# 0X_-_CPU.net
KiCad netlist of a schematic drawn in Altium Designer
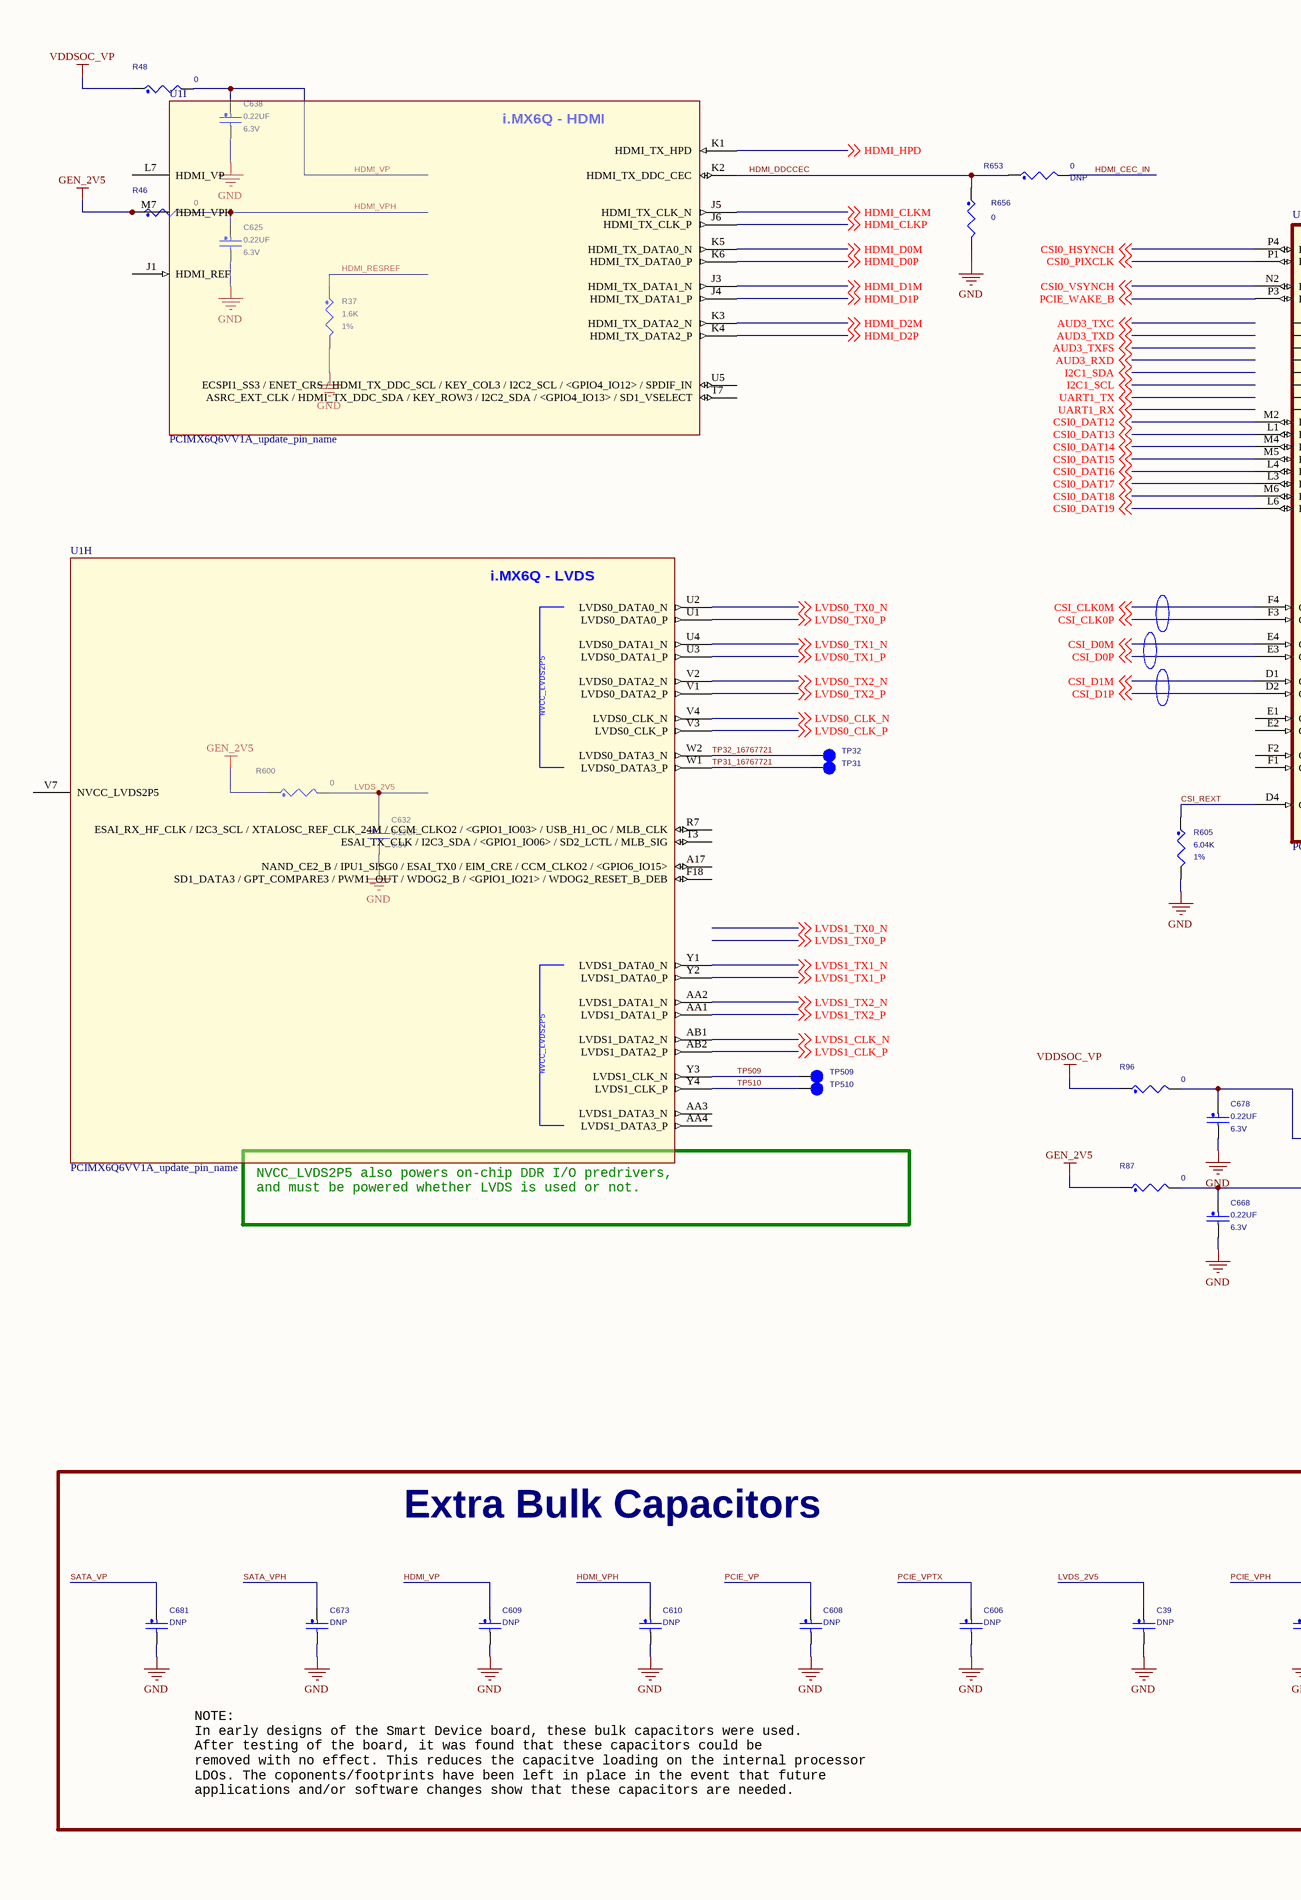
[diagram p0: [0X] - CPU.SchDoc, left]
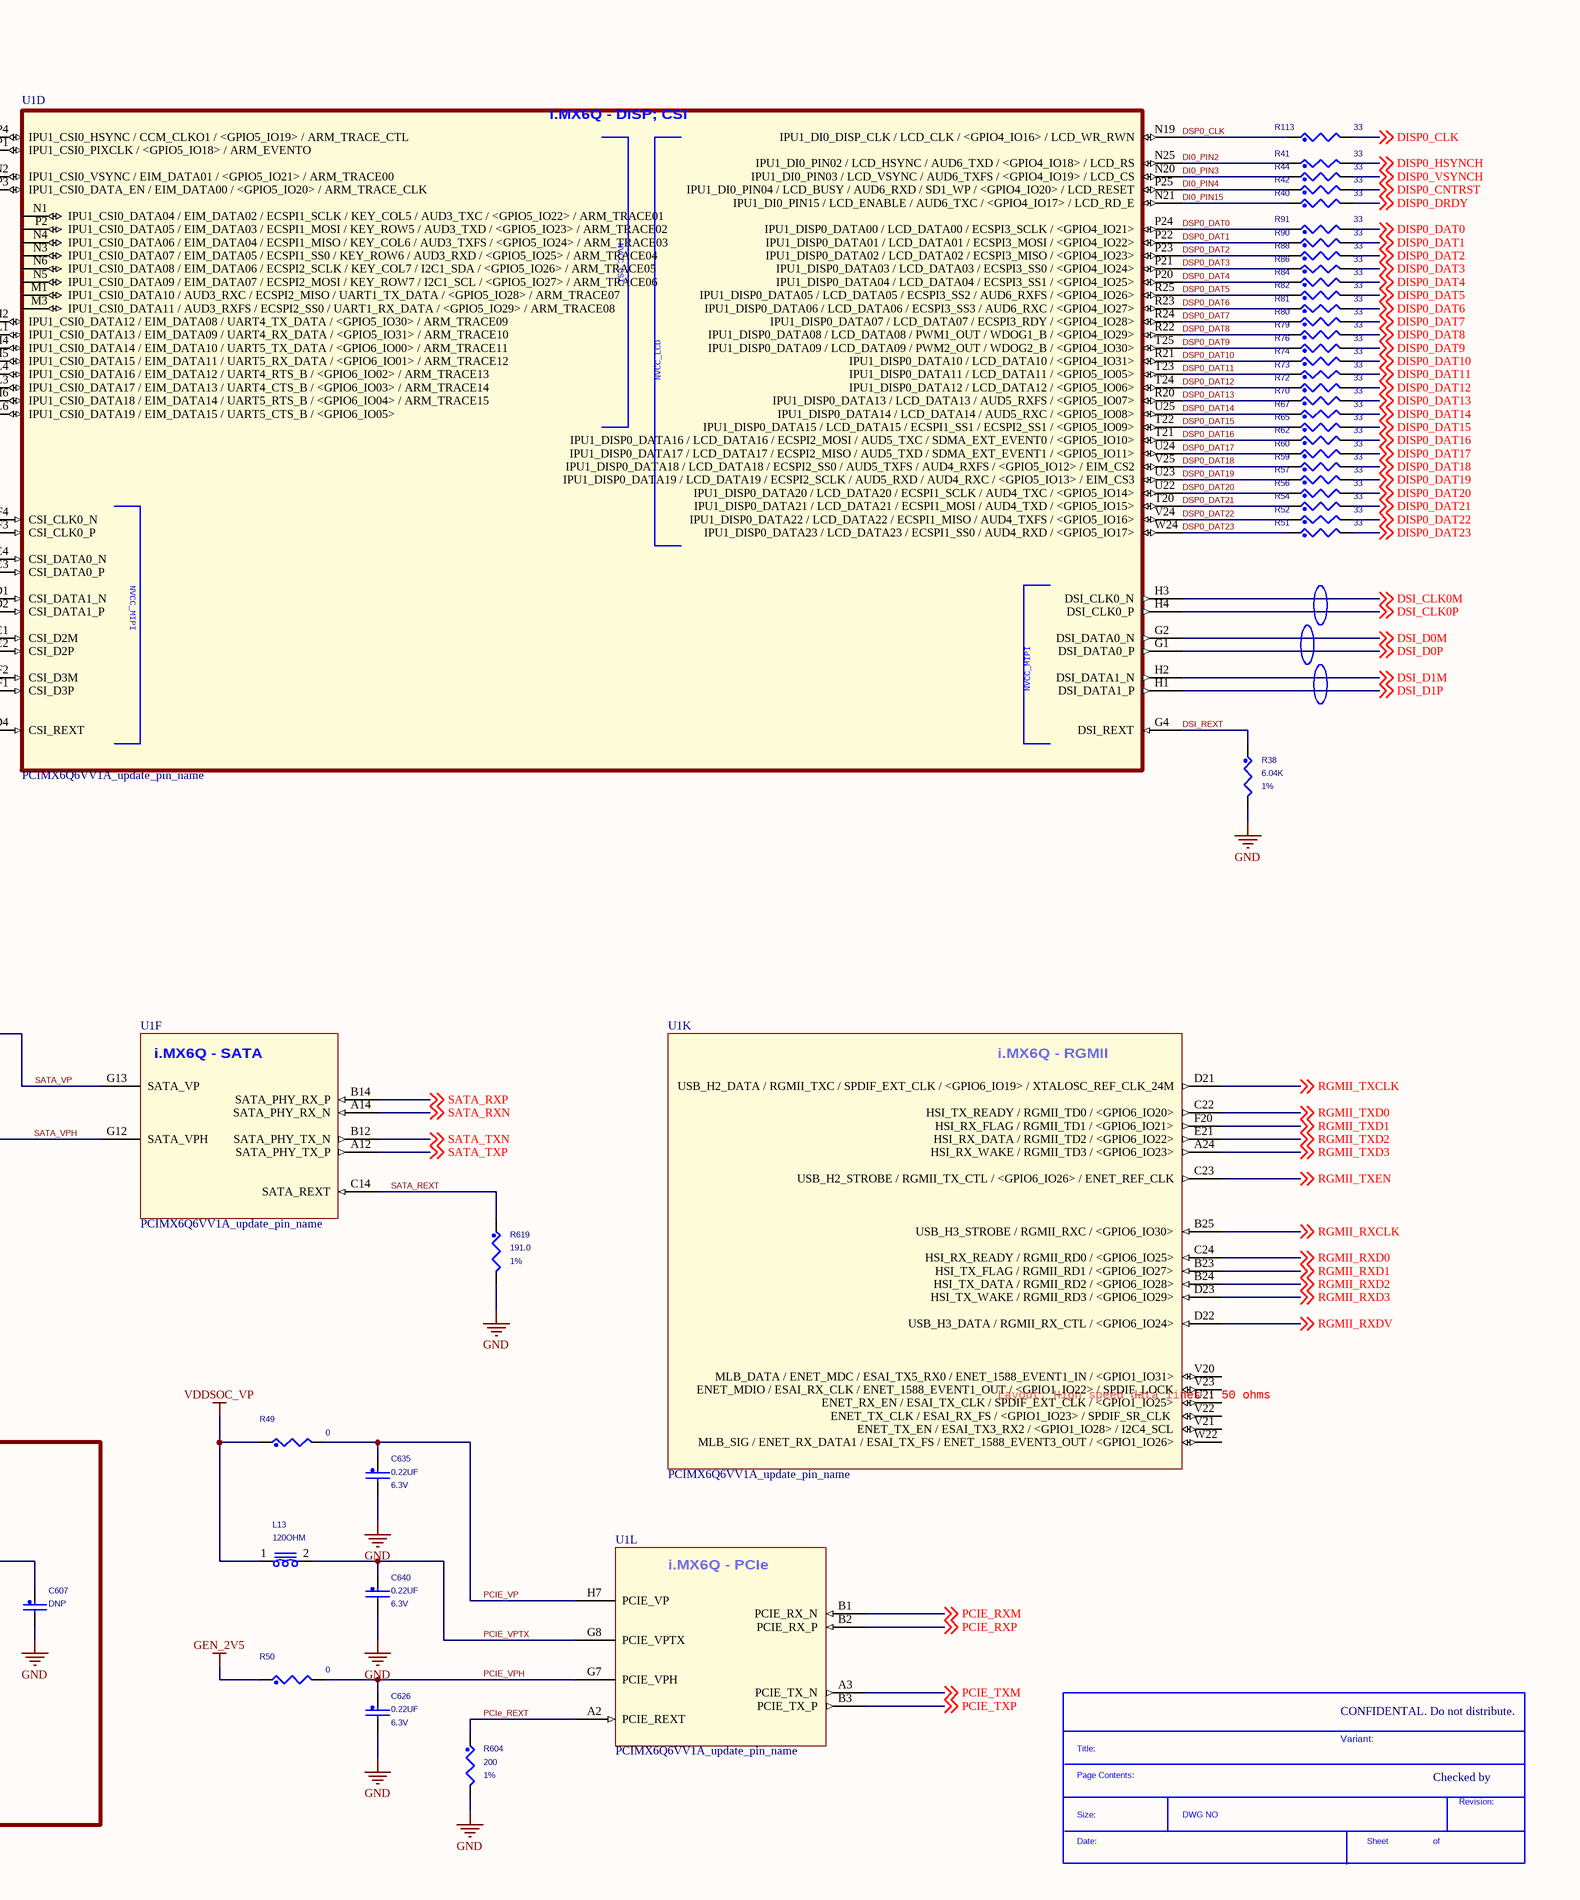
[diagram p1: [0X] - CPU.SchDoc, right]

(export (version "E")
  (design (tool "Eeschema 10.0.6"))
  (components
    (comp (ref "*") (value "SDTitleBlock") (libsource (lib "*") (part "SDTitleBlock")))
    (comp (ref "C39")
      (value "4.7UF")
      (description "CAP CER 4.7UF 10V 10% X5R 0603")
      (fields (field (name "TOLERANCE") "10%") (field (name "ASSY_OPT") "DNP") (field (name "VOLTAGE") "10V"))
      (libsource (lib "*") (part "CAP_NP"))
    )
    (comp (ref "C606")
      (value "4.7UF")
      (description "CAP CER 4.7UF 6.3V 10% X5R 0603")
      (fields
        (field (name "VOLTAGE") "6.3V")
        (field (name "TOLERANCE") "10%")
        (field (name "ASSY_OPT") "DNP")
      )
      (libsource (lib "*") (part "CAP_NP"))
    )
    (comp (ref "C607")
      (value "4.7UF")
      (description "CAP CER 4.7UF 6.3V 10% X5R 0603")
      (fields
        (field (name "VOLTAGE") "6.3V")
        (field (name "TOLERANCE") "10%")
        (field (name "ASSY_OPT") "DNP")
      )
      (libsource (lib "*") (part "CAP_NP"))
    )
    (comp (ref "C608")
      (value "4.7UF")
      (description "CAP CER 4.7UF 6.3V 10% X5R 0603")
      (fields
        (field (name "VOLTAGE") "6.3V")
        (field (name "TOLERANCE") "10%")
        (field (name "ASSY_OPT") "DNP")
      )
      (libsource (lib "*") (part "CAP_NP"))
    )
    (comp (ref "C609")
      (value "4.7UF")
      (description "CAP CER 4.7UF 6.3V 10% X5R 0603")
      (fields
        (field (name "TOLERANCE") "10%")
        (field (name "ASSY_OPT") "DNP")
        (field (name "VOLTAGE") "6.3V")
      )
      (libsource (lib "*") (part "CAP_NP"))
    )
    (comp (ref "C610")
      (value "4.7UF")
      (description "CAP CER 4.7UF 6.3V 10% X5R 0603")
      (fields
        (field (name "ASSY_OPT") "DNP")
        (field (name "TOLERANCE") "10%")
        (field (name "VOLTAGE") "6.3V")
      )
      (libsource (lib "*") (part "CAP_NP"))
    )
    (comp (ref "C625")
      (value "0.22UF")
      (description "CAP CER 0.22UF 6.3V 20% X5R 0201")
      (fields (field (name "VOLTAGE") "6.3V") (field (name "TOLERANCE") "20%") (field (name "WVDC") "6.3V"))
      (libsource (lib "*") (part "CAP_NP"))
    )
    (comp (ref "C626")
      (value "0.22UF")
      (description "CAP CER 0.22UF 6.3V 20% X5R 0201")
      (fields (field (name "WVDC") "6.3V") (field (name "TOLERANCE") "20%") (field (name "VOLTAGE") "6.3V"))
      (libsource (lib "*") (part "CAP_NP"))
    )
    (comp (ref "C632")
      (value "0.22UF")
      (description "CAP CER 0.22UF 6.3V 20% X5R 0201")
      (fields (field (name "VOLTAGE") "6.3V") (field (name "WVDC") "6.3V") (field (name "TOLERANCE") "20%"))
      (libsource (lib "*") (part "CAP_NP"))
    )
    (comp (ref "C635")
      (value "0.22UF")
      (description "CAP CER 0.22UF 6.3V 20% X5R 0201")
      (fields (field (name "WVDC") "6.3V") (field (name "TOLERANCE") "20%") (field (name "VOLTAGE") "6.3V"))
      (libsource (lib "*") (part "CAP_NP"))
    )
    (comp (ref "C638")
      (value "0.22UF")
      (description "CAP CER 0.22UF 6.3V 20% X5R 0201")
      (fields (field (name "VOLTAGE") "6.3V") (field (name "TOLERANCE") "20%") (field (name "WVDC") "6.3V"))
      (libsource (lib "*") (part "CAP_NP"))
    )
    (comp (ref "C640")
      (value "0.22UF")
      (description "CAP CER 0.22UF 6.3V 20% X5R 0201")
      (fields (field (name "WVDC") "6.3V") (field (name "TOLERANCE") "20%") (field (name "VOLTAGE") "6.3V"))
      (libsource (lib "*") (part "CAP_NP"))
    )
    (comp (ref "C668")
      (value "0.22UF")
      (description "CAP CER 0.22UF 6.3V 20% X5R 0201")
      (fields (field (name "VOLTAGE") "6.3V") (field (name "WVDC") "6.3V") (field (name "TOLERANCE") "20%"))
      (libsource (lib "*") (part "CAP_NP"))
    )
    (comp (ref "C673")
      (value "4.7UF")
      (description "CAP CER 4.7UF 6.3V 10% X5R 0603")
      (fields
        (field (name "VOLTAGE") "6.3V")
        (field (name "TOLERANCE") "10%")
        (field (name "ASSY_OPT") "DNP")
      )
      (libsource (lib "*") (part "CAP_NP"))
    )
    (comp (ref "C678")
      (value "0.22UF")
      (description "CAP CER 0.22UF 6.3V 20% X5R 0201")
      (fields (field (name "VOLTAGE") "6.3V") (field (name "WVDC") "6.3V") (field (name "TOLERANCE") "20%"))
      (libsource (lib "*") (part "CAP_NP"))
    )
    (comp (ref "C681")
      (value "4.7UF")
      (description "CAP CER 4.7UF 6.3V 10% X5R 0603")
      (fields
        (field (name "VOLTAGE") "6.3V")
        (field (name "TOLERANCE") "10%")
        (field (name "ASSY_OPT") "DNP")
      )
      (libsource (lib "*") (part "CAP_NP"))
    )
    (comp (ref "L13")
      (value "120OHM")
      (description "IND FER BEAD 120OHM@100MHZ 2A 25% 0603")
      (fields (field (name "TOLERANCE") "25%"))
      (libsource (lib "*") (part "BEAD_0"))
    )
    (comp (ref "R37")
      (value "1.6K")
      (description "RES MF 1.6K  1/16W 1% 0402")
      (fields (field (name "TOLERANCE") "1%"))
      (libsource (lib "*") (part "RES"))
    )
    (comp (ref "R38")
      (value "6.04K")
      (description "RES MF 6.04K  1/16W 1% 0402")
      (fields (field (name "TOLERANCE") "1%"))
      (libsource (lib "*") (part "RES"))
    )
    (comp (ref "R40")
      (value "33")
      (description "RES MF 33 OHM 1/16W 5% 0402")
      (fields (field (name "TOLERANCE") "5%"))
      (libsource (lib "*") (part "RES"))
    )
    (comp (ref "R41")
      (value "33")
      (description "RES MF 33 OHM 1/16W 5% 0402")
      (fields (field (name "TOLERANCE") "5%"))
      (libsource (lib "*") (part "RES"))
    )
    (comp (ref "R42")
      (value "33")
      (description "RES MF 33 OHM 1/16W 5% 0402")
      (fields (field (name "TOLERANCE") "5%"))
      (libsource (lib "*") (part "RES"))
    )
    (comp (ref "R44")
      (value "33")
      (description "RES MF 33 OHM 1/16W 5% 0402")
      (fields (field (name "TOLERANCE") "5%"))
      (libsource (lib "*") (part "RES"))
    )
    (comp (ref "R46")
      (value "0")
      (description "RES MF ZERO OHM 1/10W -- 0402")
      (libsource (lib "*") (part "RES"))
    )
    (comp (ref "R48")
      (value "0")
      (description "RES MF ZERO OHM 1/10W -- 0402")
      (libsource (lib "*") (part "RES"))
    )
    (comp (ref "R49")
      (value "0")
      (description "RES MF ZERO OHM 1/10W -- 0402")
      (libsource (lib "*") (part "RES"))
    )
    (comp (ref "R50")
      (value "0")
      (description "RES MF ZERO OHM 1/10W -- 0402")
      (libsource (lib "*") (part "RES"))
    )
    (comp (ref "R51")
      (value "33")
      (description "RES MF 33 OHM 1/16W 5% 0402")
      (fields (field (name "TOLERANCE") "5%"))
      (libsource (lib "*") (part "RES"))
    )
    (comp (ref "R52")
      (value "33")
      (description "RES MF 33 OHM 1/16W 5% 0402")
      (fields (field (name "TOLERANCE") "5%"))
      (libsource (lib "*") (part "RES"))
    )
    (comp (ref "R54")
      (value "33")
      (description "RES MF 33 OHM 1/16W 5% 0402")
      (fields (field (name "TOLERANCE") "5%"))
      (libsource (lib "*") (part "RES"))
    )
    (comp (ref "R56")
      (value "33")
      (description "RES MF 33 OHM 1/16W 5% 0402")
      (fields (field (name "TOLERANCE") "5%"))
      (libsource (lib "*") (part "RES"))
    )
    (comp (ref "R57")
      (value "33")
      (description "RES MF 33 OHM 1/16W 5% 0402")
      (fields (field (name "TOLERANCE") "5%"))
      (libsource (lib "*") (part "RES"))
    )
    (comp (ref "R59")
      (value "33")
      (description "RES MF 33 OHM 1/16W 5% 0402")
      (fields (field (name "TOLERANCE") "5%"))
      (libsource (lib "*") (part "RES"))
    )
    (comp (ref "R60")
      (value "33")
      (description "RES MF 33 OHM 1/16W 5% 0402")
      (fields (field (name "TOLERANCE") "5%"))
      (libsource (lib "*") (part "RES"))
    )
    (comp (ref "R62")
      (value "33")
      (description "RES MF 33 OHM 1/16W 5% 0402")
      (fields (field (name "TOLERANCE") "5%"))
      (libsource (lib "*") (part "RES"))
    )
    (comp (ref "R65")
      (value "33")
      (description "RES MF 33 OHM 1/16W 5% 0402")
      (fields (field (name "TOLERANCE") "5%"))
      (libsource (lib "*") (part "RES"))
    )
    (comp (ref "R67")
      (value "33")
      (description "RES MF 33 OHM 1/16W 5% 0402")
      (fields (field (name "TOLERANCE") "5%"))
      (libsource (lib "*") (part "RES"))
    )
    (comp (ref "R70")
      (value "33")
      (description "RES MF 33 OHM 1/16W 5% 0402")
      (fields (field (name "TOLERANCE") "5%"))
      (libsource (lib "*") (part "RES"))
    )
    (comp (ref "R72")
      (value "33")
      (description "RES MF 33 OHM 1/16W 5% 0402")
      (fields (field (name "TOLERANCE") "5%"))
      (libsource (lib "*") (part "RES"))
    )
    (comp (ref "R73")
      (value "33")
      (description "RES MF 33 OHM 1/16W 5% 0402")
      (fields (field (name "TOLERANCE") "5%"))
      (libsource (lib "*") (part "RES"))
    )
    (comp (ref "R74")
      (value "33")
      (description "RES MF 33 OHM 1/16W 5% 0402")
      (fields (field (name "TOLERANCE") "5%"))
      (libsource (lib "*") (part "RES"))
    )
    (comp (ref "R76")
      (value "33")
      (description "RES MF 33 OHM 1/16W 5% 0402")
      (fields (field (name "TOLERANCE") "5%"))
      (libsource (lib "*") (part "RES"))
    )
    (comp (ref "R79")
      (value "33")
      (description "RES MF 33 OHM 1/16W 5% 0402")
      (fields (field (name "TOLERANCE") "5%"))
      (libsource (lib "*") (part "RES"))
    )
    (comp (ref "R80")
      (value "33")
      (description "RES MF 33 OHM 1/16W 5% 0402")
      (fields (field (name "TOLERANCE") "5%"))
      (libsource (lib "*") (part "RES"))
    )
    (comp (ref "R81")
      (value "33")
      (description "RES MF 33 OHM 1/16W 5% 0402")
      (fields (field (name "TOLERANCE") "5%"))
      (libsource (lib "*") (part "RES"))
    )
    (comp (ref "R82")
      (value "33")
      (description "RES MF 33 OHM 1/16W 5% 0402")
      (fields (field (name "TOLERANCE") "5%"))
      (libsource (lib "*") (part "RES"))
    )
    (comp (ref "R84")
      (value "33")
      (description "RES MF 33 OHM 1/16W 5% 0402")
      (fields (field (name "TOLERANCE") "5%"))
      (libsource (lib "*") (part "RES"))
    )
    (comp (ref "R86")
      (value "33")
      (description "RES MF 33 OHM 1/16W 5% 0402")
      (fields (field (name "TOLERANCE") "5%"))
      (libsource (lib "*") (part "RES"))
    )
    (comp (ref "R87")
      (value "0")
      (description "RES MF ZERO OHM 1/10W -- 0402")
      (libsource (lib "*") (part "RES"))
    )
    (comp (ref "R88")
      (value "33")
      (description "RES MF 33 OHM 1/16W 5% 0402")
      (fields (field (name "TOLERANCE") "5%"))
      (libsource (lib "*") (part "RES"))
    )
    (comp (ref "R90")
      (value "33")
      (description "RES MF 33 OHM 1/16W 5% 0402")
      (fields (field (name "TOLERANCE") "5%"))
      (libsource (lib "*") (part "RES"))
    )
    (comp (ref "R91")
      (value "33")
      (description "RES MF 33 OHM 1/16W 5% 0402")
      (fields (field (name "TOLERANCE") "5%"))
      (libsource (lib "*") (part "RES"))
    )
    (comp (ref "R96")
      (value "0")
      (description "RES MF ZERO OHM 1/10W -- 0402")
      (libsource (lib "*") (part "RES"))
    )
    (comp (ref "R113")
      (value "33")
      (description "RES MF 33 OHM 1/16W 5% 0402")
      (fields (field (name "TOLERANCE") "5%"))
      (libsource (lib "*") (part "RES"))
    )
    (comp (ref "R600")
      (value "0")
      (description "RES MF ZERO OHM 1/10W -- 0402")
      (libsource (lib "*") (part "RES"))
    )
    (comp (ref "R604")
      (value "200")
      (description "RES MF 200 OHM 1/16W 1% 0402")
      (fields (field (name "TOLERANCE") "1%"))
      (libsource (lib "*") (part "RES"))
    )
    (comp (ref "R605")
      (value "6.04K")
      (description "RES MF 6.04K  1/16W 1% 0402")
      (fields (field (name "TOLERANCE") "1%"))
      (libsource (lib "*") (part "RES"))
    )
    (comp (ref "R619")
      (value "191.0")
      (description "RES MF 191.0 OHM  1/10W 1% 0603")
      (fields (field (name "TOLERANCE") "1%"))
      (libsource (lib "*") (part "RES"))
    )
    (comp (ref "R653")
      (value "0")
      (description "RES MF ZERO OHM 1/10W -- 0402")
      (fields (field (name "ASSY_OPT") "DNP"))
      (libsource (lib "*") (part "RES"))
    )
    (comp (ref "R656")
      (value "0")
      (description "RES MF ZERO OHM 1/10W -- 0402")
      (libsource (lib "*") (part "RES"))
    )
    (comp (ref "TP31")
      (value "tpad_020")
      (description "TEST POINT PAD 0.5MM DIA SMT, NO PART TO ORDER")
      (libsource (lib "*") (part "TESTLOOP"))
    )
    (comp (ref "TP32")
      (value "tpad_020")
      (description "TEST POINT PAD 0.5MM DIA SMT, NO PART TO ORDER")
      (libsource (lib "*") (part "TESTLOOP"))
    )
    (comp (ref "TP509")
      (value "tpad_020")
      (description "TEST POINT PAD 0.5MM DIA SMT, NO PART TO ORDER")
      (libsource (lib "*") (part "TESTLOOP"))
    )
    (comp (ref "TP510")
      (value "tpad_020")
      (description "TEST POINT PAD 0.5MM DIA SMT, NO PART TO ORDER")
      (libsource (lib "*") (part "TESTLOOP"))
    )
    (comp (ref "U1")
      (value "PCIMX6Q6VV1A_update_pin_name")
      (libsource (lib "SCH-27516_C3_16_2_Library") (part "PCIMX6Q6VV1A_update_pin_name"))
    )
  )
  (nets
    (net (code "1") (name "/CSI_REXT") (class "Default")
      (node (ref "R605") (pin "1") (pinfunction "1_1") (pintype "passive"))
      (node (ref "U1") (pin "D4") (pinfunction "CSI_REXT_D4") (pintype "input"))
    )
    (net (code "2") (name "/DI0_PIN2") (class "Default")
      (node (ref "R41") (pin "1") (pinfunction "1_1") (pintype "passive"))
      (node (ref "U1") (pin "N25") (pinfunction "IPU1_DI0_PIN02_/_LCD_HSYNC_/_AUD6_TXD_/_<GPIO4_IO18>_/_LCD_RS_N25") (pintype "bidirectional"))
    )
    (net (code "3") (name "/DI0_PIN3") (class "Default")
      (node (ref "R44") (pin "1") (pinfunction "1_1") (pintype "passive"))
      (node (ref "U1") (pin "N20") (pinfunction "IPU1_DI0_PIN03_/_LCD_VSYNC_/_AUD6_TXFS_/_<GPIO4_IO19>_/_LCD_CS_N20") (pintype "bidirectional"))
    )
    (net (code "4") (name "/DI0_PIN4") (class "Default")
      (node (ref "R42") (pin "1") (pinfunction "1_1") (pintype "passive"))
      (node (ref "U1") (pin "P25") (pinfunction "IPU1_DI0_PIN04_/_LCD_BUSY_/_AUD6_RXD_/_SD1_WP_/_<GPIO4_IO20>_/_LCD_RESET_P25") (pintype "bidirectional"))
    )
    (net (code "5") (name "/DI0_PIN15") (class "Default")
      (node (ref "R40") (pin "1") (pinfunction "1_1") (pintype "passive"))
      (node (ref "U1") (pin "N21") (pinfunction "IPU1_DI0_PIN15_/_LCD_ENABLE_/_AUD6_TXC_/_<GPIO4_IO17>_/_LCD_RD_E_N21") (pintype "bidirectional"))
    )
    (net (code "6") (name "/DSI_REXT") (class "Default")
      (node (ref "R38") (pin "1") (pinfunction "1_1") (pintype "passive"))
      (node (ref "U1") (pin "G4") (pinfunction "DSI_REXT_G4") (pintype "input"))
    )
    (net (code "7") (name "/DSP0_CLK") (class "Default")
      (node (ref "R113") (pin "1") (pinfunction "1_1") (pintype "passive"))
      (node (ref "U1") (pin "N19") (pinfunction "IPU1_DI0_DISP_CLK_/_LCD_CLK_/_<GPIO4_IO16>_/_LCD_WR_RWN_N19") (pintype "bidirectional"))
    )
    (net (code "8") (name "/DSP0_DAT0") (class "Default")
      (node (ref "R91") (pin "1") (pinfunction "1_1") (pintype "passive"))
      (node (ref "U1") (pin "P24") (pinfunction "IPU1_DISP0_DATA00_/_LCD_DATA00_/_ECSPI3_SCLK_/_<GPIO4_IO21>_P24") (pintype "bidirectional"))
    )
    (net (code "9") (name "/DSP0_DAT1") (class "Default")
      (node (ref "R90") (pin "1") (pinfunction "1_1") (pintype "passive"))
      (node (ref "U1") (pin "P22") (pinfunction "IPU1_DISP0_DATA01_/_LCD_DATA01_/_ECSPI3_MOSI_/_<GPIO4_IO22>_P22") (pintype "bidirectional"))
    )
    (net (code "10") (name "/DSP0_DAT2") (class "Default")
      (node (ref "R88") (pin "1") (pinfunction "1_1") (pintype "passive"))
      (node (ref "U1") (pin "P23") (pinfunction "IPU1_DISP0_DATA02_/_LCD_DATA02_/_ECSPI3_MISO_/_<GPIO4_IO23>_P23") (pintype "bidirectional"))
    )
    (net (code "11") (name "/DSP0_DAT3") (class "Default")
      (node (ref "R86") (pin "1") (pinfunction "1_1") (pintype "passive"))
      (node (ref "U1") (pin "P21") (pinfunction "IPU1_DISP0_DATA03_/_LCD_DATA03_/_ECSPI3_SS0_/_<GPIO4_IO24>_P21") (pintype "bidirectional"))
    )
    (net (code "12") (name "/DSP0_DAT4") (class "Default")
      (node (ref "R84") (pin "1") (pinfunction "1_1") (pintype "passive"))
      (node (ref "U1") (pin "P20") (pinfunction "IPU1_DISP0_DATA04_/_LCD_DATA04_/_ECSPI3_SS1_/_<GPIO4_IO25>_P20") (pintype "bidirectional"))
    )
    (net (code "13") (name "/DSP0_DAT5") (class "Default")
      (node (ref "R82") (pin "1") (pinfunction "1_1") (pintype "passive"))
      (node (ref "U1") (pin "R25") (pinfunction "IPU1_DISP0_DATA05_/_LCD_DATA05_/_ECSPI3_SS2_/_AUD6_RXFS_/_<GPIO4_IO26>_R25") (pintype "bidirectional"))
    )
    (net (code "14") (name "/DSP0_DAT6") (class "Default")
      (node (ref "R81") (pin "1") (pinfunction "1_1") (pintype "passive"))
      (node (ref "U1") (pin "R23") (pinfunction "IPU1_DISP0_DATA06_/_LCD_DATA06_/_ECSPI3_SS3_/_AUD6_RXC_/_<GPIO4_IO27>_R23") (pintype "bidirectional"))
    )
    (net (code "15") (name "/DSP0_DAT7") (class "Default")
      (node (ref "R80") (pin "1") (pinfunction "1_1") (pintype "passive"))
      (node (ref "U1") (pin "R24") (pinfunction "IPU1_DISP0_DATA07_/_LCD_DATA07_/_ECSPI3_RDY_/_<GPIO4_IO28>_R24") (pintype "bidirectional"))
    )
    (net (code "16") (name "/DSP0_DAT8") (class "Default")
      (node (ref "R79") (pin "1") (pinfunction "1_1") (pintype "passive"))
      (node (ref "U1") (pin "R22") (pinfunction "IPU1_DISP0_DATA08_/_LCD_DATA08_/_PWM1_OUT_/_WDOG1_B_/_<GPIO4_IO29>_R22") (pintype "bidirectional"))
    )
    (net (code "17") (name "/DSP0_DAT9") (class "Default")
      (node (ref "R76") (pin "1") (pinfunction "1_1") (pintype "passive"))
      (node (ref "U1") (pin "T25") (pinfunction "IPU1_DISP0_DATA09_/_LCD_DATA09_/_PWM2_OUT_/_WDOG2_B_/_<GPIO4_IO30>_T25") (pintype "bidirectional"))
    )
    (net (code "18") (name "/DSP0_DAT10") (class "Default")
      (node (ref "R74") (pin "1") (pinfunction "1_1") (pintype "passive"))
      (node (ref "U1") (pin "R21") (pinfunction "IPU1_DISP0_DATA10_/_LCD_DATA10_/_<GPIO4_IO31>_R21") (pintype "bidirectional"))
    )
    (net (code "19") (name "/DSP0_DAT11") (class "Default")
      (node (ref "R73") (pin "1") (pinfunction "1_1") (pintype "passive"))
      (node (ref "U1") (pin "T23") (pinfunction "IPU1_DISP0_DATA11_/_LCD_DATA11_/_<GPIO5_IO05>_T23") (pintype "bidirectional"))
    )
    (net (code "20") (name "/DSP0_DAT12") (class "Default")
      (node (ref "R72") (pin "1") (pinfunction "1_1") (pintype "passive"))
      (node (ref "U1") (pin "T24") (pinfunction "IPU1_DISP0_DATA12_/_LCD_DATA12_/_<GPIO5_IO06>_T24") (pintype "bidirectional"))
    )
    (net (code "21") (name "/DSP0_DAT13") (class "Default")
      (node (ref "R70") (pin "1") (pinfunction "1_1") (pintype "passive"))
      (node (ref "U1") (pin "R20") (pinfunction "IPU1_DISP0_DATA13_/_LCD_DATA13_/_AUD5_RXFS_/_<GPIO5_IO07>_R20") (pintype "bidirectional"))
    )
    (net (code "22") (name "/DSP0_DAT14") (class "Default")
      (node (ref "R67") (pin "1") (pinfunction "1_1") (pintype "passive"))
      (node (ref "U1") (pin "U25") (pinfunction "IPU1_DISP0_DATA14_/_LCD_DATA14_/_AUD5_RXC_/_<GPIO5_IO08>_U25") (pintype "bidirectional"))
    )
    (net (code "23") (name "/DSP0_DAT15") (class "Default")
      (node (ref "R65") (pin "1") (pinfunction "1_1") (pintype "passive"))
      (node (ref "U1") (pin "T22") (pinfunction "IPU1_DISP0_DATA15_/_LCD_DATA15_/_ECSPI1_SS1_/_ECSPI2_SS1_/_<GPIO5_IO09>_T22") (pintype "bidirectional"))
    )
    (net (code "24") (name "/DSP0_DAT16") (class "Default")
      (node (ref "R62") (pin "1") (pinfunction "1_1") (pintype "passive"))
      (node (ref "U1") (pin "T21") (pinfunction "IPU1_DISP0_DATA16_/_LCD_DATA16_/_ECSPI2_MOSI_/_AUD5_TXC_/_SDMA_EXT_EVENT0_/_<GPIO5_IO10>_T21") (pintype "bidirectional"))
    )
    (net (code "25") (name "/DSP0_DAT17") (class "Default")
      (node (ref "R60") (pin "1") (pinfunction "1_1") (pintype "passive"))
      (node (ref "U1") (pin "U24") (pinfunction "IPU1_DISP0_DATA17_/_LCD_DATA17_/_ECSPI2_MISO_/_AUD5_TXD_/_SDMA_EXT_EVENT1_/_<GPIO5_IO11>_U24") (pintype "bidirectional"))
    )
    (net (code "26") (name "/DSP0_DAT18") (class "Default")
      (node (ref "R59") (pin "1") (pinfunction "1_1") (pintype "passive"))
      (node (ref "U1") (pin "V25") (pinfunction "IPU1_DISP0_DATA18_/_LCD_DATA18_/_ECSPI2_SS0_/_AUD5_TXFS_/_AUD4_RXFS_/_<GPIO5_IO12>_/_EIM_CS2_V25") (pintype "bidirectional"))
    )
    (net (code "27") (name "/DSP0_DAT19") (class "Default")
      (node (ref "R57") (pin "1") (pinfunction "1_1") (pintype "passive"))
      (node (ref "U1") (pin "U23") (pinfunction "IPU1_DISP0_DATA19_/_LCD_DATA19_/_ECSPI2_SCLK_/_AUD5_RXD_/_AUD4_RXC_/_<GPIO5_IO13>_/_EIM_CS3_U23") (pintype "bidirectional"))
    )
    (net (code "28") (name "/DSP0_DAT20") (class "Default")
      (node (ref "R56") (pin "1") (pinfunction "1_1") (pintype "passive"))
      (node (ref "U1") (pin "U22") (pinfunction "IPU1_DISP0_DATA20_/_LCD_DATA20_/_ECSPI1_SCLK_/_AUD4_TXC_/_<GPIO5_IO14>_U22") (pintype "bidirectional"))
    )
    (net (code "29") (name "/DSP0_DAT21") (class "Default")
      (node (ref "R54") (pin "1") (pinfunction "1_1") (pintype "passive"))
      (node (ref "U1") (pin "T20") (pinfunction "IPU1_DISP0_DATA21_/_LCD_DATA21_/_ECSPI1_MOSI_/_AUD4_TXD_/_<GPIO5_IO15>_T20") (pintype "bidirectional"))
    )
    (net (code "30") (name "/DSP0_DAT22") (class "Default")
      (node (ref "R52") (pin "1") (pinfunction "1_1") (pintype "passive"))
      (node (ref "U1") (pin "V24") (pinfunction "IPU1_DISP0_DATA22_/_LCD_DATA22_/_ECSPI1_MISO_/_AUD4_TXFS_/_<GPIO5_IO16>_V24") (pintype "bidirectional"))
    )
    (net (code "31") (name "/DSP0_DAT23") (class "Default")
      (node (ref "R51") (pin "1") (pinfunction "1_1") (pintype "passive"))
      (node (ref "U1") (pin "W24") (pinfunction "IPU1_DISP0_DATA23_/_LCD_DATA23_/_ECSPI1_SS0_/_AUD4_RXD_/_<GPIO5_IO17>_W24") (pintype "bidirectional"))
    )
    (net (code "32") (name "/HDMI_CEC_IN") (class "Default")
      (node (ref "R653") (pin "2") (pinfunction "2_2") (pintype "passive"))
    )
    (net (code "33") (name "/HDMI_DDCCEC") (class "Default")
      (node (ref "R653") (pin "1") (pinfunction "1_1") (pintype "passive"))
      (node (ref "R656") (pin "1") (pinfunction "1_1") (pintype "passive"))
      (node (ref "U1") (pin "K2") (pinfunction "HDMI_TX_DDC_CEC_K2") (pintype "bidirectional"))
    )
    (net (code "34") (name "/HDMI_RESREF") (class "Default")
      (node (ref "R37") (pin "1") (pinfunction "1_1") (pintype "passive"))
    )
    (net (code "35") (name "/HDMI_VP") (class "Default")
      (node (ref "C609") (pin "1") (pinfunction "1_1") (pintype "passive"))
      (node (ref "C638") (pin "1") (pinfunction "1_1") (pintype "passive"))
      (node (ref "R48") (pin "2") (pinfunction "2_2") (pintype "passive"))
    )
    (net (code "36") (name "/HDMI_VPH") (class "Default")
      (node (ref "C610") (pin "1") (pinfunction "1_1") (pintype "passive"))
      (node (ref "C625") (pin "1") (pinfunction "1_1") (pintype "passive"))
      (node (ref "R46") (pin "2") (pinfunction "2_2") (pintype "passive"))
    )
    (net (code "37") (name "/LVDS_2V5") (class "Default")
      (node (ref "C39") (pin "1") (pinfunction "1_1") (pintype "passive"))
      (node (ref "C632") (pin "1") (pinfunction "1_1") (pintype "passive"))
      (node (ref "R600") (pin "2") (pinfunction "2_2") (pintype "passive"))
    )
    (net (code "38") (name "/PCIE_VP") (class "Default")
      (node (ref "C608") (pin "1") (pinfunction "1_1") (pintype "passive"))
      (node (ref "C635") (pin "1") (pinfunction "1_1") (pintype "passive"))
      (node (ref "R49") (pin "2") (pinfunction "2_2") (pintype "passive"))
      (node (ref "U1") (pin "H7") (pinfunction "PCIE_VP_H7") (pintype "power_in"))
    )
    (net (code "39") (name "/PCIE_VPH") (class "Default")
      (node (ref "C607") (pin "1") (pinfunction "1_1") (pintype "passive"))
      (node (ref "C626") (pin "1") (pinfunction "1_1") (pintype "passive"))
      (node (ref "R50") (pin "2") (pinfunction "2_2") (pintype "passive"))
      (node (ref "U1") (pin "G7") (pinfunction "PCIE_VPH_G7") (pintype "power_in"))
    )
    (net (code "40") (name "/PCIE_VPTX") (class "Default")
      (node (ref "C606") (pin "1") (pinfunction "1_1") (pintype "passive"))
      (node (ref "C640") (pin "1") (pinfunction "1_1") (pintype "passive"))
      (node (ref "L13") (pin "2") (pinfunction "2_2") (pintype "passive"))
      (node (ref "U1") (pin "G8") (pinfunction "PCIE_VPTX_G8") (pintype "power_in"))
    )
    (net (code "41") (name "/PCIe_REXT") (class "Default")
      (node (ref "R604") (pin "1") (pinfunction "1_1") (pintype "passive"))
      (node (ref "U1") (pin "A2") (pinfunction "PCIE_REXT_A2") (pintype "input"))
    )
    (net (code "42") (name "/SATA_REXT") (class "Default")
      (node (ref "R619") (pin "1") (pinfunction "1_1") (pintype "passive"))
      (node (ref "U1") (pin "C14") (pinfunction "SATA_REXT_C14") (pintype "input"))
    )
    (net (code "43") (name "/SATA_VP") (class "Default")
      (node (ref "C678") (pin "1") (pinfunction "1_1") (pintype "passive"))
      (node (ref "C681") (pin "1") (pinfunction "1_1") (pintype "passive"))
      (node (ref "R96") (pin "2") (pinfunction "2_2") (pintype "passive"))
      (node (ref "U1") (pin "G13") (pinfunction "SATA_VP_G13") (pintype "power_in"))
    )
    (net (code "44") (name "/SATA_VPH") (class "Default")
      (node (ref "C668") (pin "1") (pinfunction "1_1") (pintype "passive"))
      (node (ref "C673") (pin "1") (pinfunction "1_1") (pintype "passive"))
      (node (ref "R87") (pin "2") (pinfunction "2_2") (pintype "passive"))
      (node (ref "U1") (pin "G12") (pinfunction "SATA_VPH_G12") (pintype "power_in"))
    )
    (net (code "45") (name "/TP31_16767721") (class "Default")
      (node (ref "TP31") (pin "1") (pinfunction "Pin1_1") (pintype "passive"))
      (node (ref "U1") (pin "W1") (pinfunction "LVDS0_DATA3_P_W1") (pintype "output"))
    )
    (net (code "46") (name "/TP32_16767721") (class "Default")
      (node (ref "TP32") (pin "1") (pinfunction "Pin1_1") (pintype "passive"))
      (node (ref "U1") (pin "W2") (pinfunction "LVDS0_DATA3_N_W2") (pintype "output"))
    )
    (net (code "47") (name "/TP509") (class "Default")
      (node (ref "TP509") (pin "1") (pinfunction "Pin1_1") (pintype "passive"))
      (node (ref "U1") (pin "Y3") (pinfunction "LVDS1_CLK_N_Y3") (pintype "output"))
    )
    (net (code "48") (name "/TP510") (class "Default")
      (node (ref "TP510") (pin "1") (pinfunction "Pin1_1") (pintype "passive"))
      (node (ref "U1") (pin "Y4") (pinfunction "LVDS1_CLK_P_Y4") (pintype "output"))
    )
    (net (code "53") (name "CSI0_DAT12") (class "Default")
      (node (ref "U1") (pin "M2") (pinfunction "IPU1_CSI0_DATA12_/_EIM_DATA08_/_UART4_TX_DATA_/_<GPIO5_IO30>_/_ARM_TRACE09_M2") (pintype "bidirectional"))
    )
    (net (code "54") (name "CSI0_DAT13") (class "Default")
      (node (ref "U1") (pin "L1") (pinfunction "IPU1_CSI0_DATA13_/_EIM_DATA09_/_UART4_RX_DATA_/_<GPIO5_IO31>_/_ARM_TRACE10_L1") (pintype "bidirectional"))
    )
    (net (code "55") (name "CSI0_DAT14") (class "Default")
      (node (ref "U1") (pin "M4") (pinfunction "IPU1_CSI0_DATA14_/_EIM_DATA10_/_UART5_TX_DATA_/_<GPIO6_IO00>_/_ARM_TRACE11_M4") (pintype "bidirectional"))
    )
    (net (code "56") (name "CSI0_DAT15") (class "Default")
      (node (ref "U1") (pin "M5") (pinfunction "IPU1_CSI0_DATA15_/_EIM_DATA11_/_UART5_RX_DATA_/_<GPIO6_IO01>_/_ARM_TRACE12_M5") (pintype "bidirectional"))
    )
    (net (code "57") (name "CSI0_DAT16") (class "Default")
      (node (ref "U1") (pin "L4") (pinfunction "IPU1_CSI0_DATA16_/_EIM_DATA12_/_UART4_RTS_B_/_<GPIO6_IO02>_/_ARM_TRACE13_L4") (pintype "bidirectional"))
    )
    (net (code "58") (name "CSI0_DAT17") (class "Default")
      (node (ref "U1") (pin "L3") (pinfunction "IPU1_CSI0_DATA17_/_EIM_DATA13_/_UART4_CTS_B_/_<GPIO6_IO03>_/_ARM_TRACE14_L3") (pintype "bidirectional"))
    )
    (net (code "59") (name "CSI0_DAT18") (class "Default")
      (node (ref "U1") (pin "M6") (pinfunction "IPU1_CSI0_DATA18_/_EIM_DATA14_/_UART5_RTS_B_/_<GPIO6_IO04>_/_ARM_TRACE15_M6") (pintype "bidirectional"))
    )
    (net (code "60") (name "CSI0_DAT19") (class "Default")
      (node (ref "U1") (pin "L6") (pinfunction "IPU1_CSI0_DATA19_/_EIM_DATA15_/_UART5_CTS_B_/_<GPIO6_IO05>_L6") (pintype "bidirectional"))
    )
    (net (code "61") (name "CSI0_HSYNCH") (class "Default")
      (node (ref "U1") (pin "P4") (pinfunction "IPU1_CSI0_HSYNC_/_CCM_CLKO1_/_<GPIO5_IO19>_/_ARM_TRACE_CTL_P4") (pintype "bidirectional"))
    )
    (net (code "62") (name "CSI0_PIXCLK") (class "Default")
      (node (ref "U1") (pin "P1") (pinfunction "IPU1_CSI0_PIXCLK_/_<GPIO5_IO18>_/_ARM_EVENTO_P1") (pintype "bidirectional"))
    )
    (net (code "63") (name "CSI0_VSYNCH") (class "Default")
      (node (ref "U1") (pin "N2") (pinfunction "IPU1_CSI0_VSYNC_/_EIM_DATA01_/_<GPIO5_IO21>_/_ARM_TRACE00_N2") (pintype "bidirectional"))
    )
    (net (code "64") (name "CSI_CLK0M") (class "Default")
      (node (ref "U1") (pin "F4") (pinfunction "CSI_CLK0_N_F4") (pintype "input"))
    )
    (net (code "65") (name "CSI_CLK0P") (class "Default")
      (node (ref "U1") (pin "F3") (pinfunction "CSI_CLK0_P_F3") (pintype "input"))
    )
    (net (code "66") (name "CSI_D0M") (class "Default")
      (node (ref "U1") (pin "E4") (pinfunction "CSI_DATA0_N_E4") (pintype "input"))
    )
    (net (code "67") (name "CSI_D0P") (class "Default")
      (node (ref "U1") (pin "E3") (pinfunction "CSI_DATA0_P_E3") (pintype "input"))
    )
    (net (code "68") (name "CSI_D1M") (class "Default")
      (node (ref "U1") (pin "D1") (pinfunction "CSI_DATA1_N_D1") (pintype "input"))
    )
    (net (code "69") (name "CSI_D1P") (class "Default")
      (node (ref "U1") (pin "D2") (pinfunction "CSI_DATA1_P_D2") (pintype "input"))
    )
    (net (code "70") (name "DISP0_CLK") (class "Default")
      (node (ref "R113") (pin "2") (pinfunction "2_2") (pintype "passive"))
    )
    (net (code "71") (name "DISP0_CNTRST") (class "Default")
      (node (ref "R42") (pin "2") (pinfunction "2_2") (pintype "passive"))
    )
    (net (code "72") (name "DISP0_DAT0") (class "Default")
      (node (ref "R91") (pin "2") (pinfunction "2_2") (pintype "passive"))
    )
    (net (code "73") (name "DISP0_DAT1") (class "Default")
      (node (ref "R90") (pin "2") (pinfunction "2_2") (pintype "passive"))
    )
    (net (code "74") (name "DISP0_DAT2") (class "Default")
      (node (ref "R88") (pin "2") (pinfunction "2_2") (pintype "passive"))
    )
    (net (code "75") (name "DISP0_DAT3") (class "Default")
      (node (ref "R86") (pin "2") (pinfunction "2_2") (pintype "passive"))
    )
    (net (code "76") (name "DISP0_DAT4") (class "Default")
      (node (ref "R84") (pin "2") (pinfunction "2_2") (pintype "passive"))
    )
    (net (code "77") (name "DISP0_DAT5") (class "Default")
      (node (ref "R82") (pin "2") (pinfunction "2_2") (pintype "passive"))
    )
    (net (code "78") (name "DISP0_DAT6") (class "Default")
      (node (ref "R81") (pin "2") (pinfunction "2_2") (pintype "passive"))
    )
    (net (code "79") (name "DISP0_DAT7") (class "Default")
      (node (ref "R80") (pin "2") (pinfunction "2_2") (pintype "passive"))
    )
    (net (code "80") (name "DISP0_DAT8") (class "Default")
      (node (ref "R79") (pin "2") (pinfunction "2_2") (pintype "passive"))
    )
    (net (code "81") (name "DISP0_DAT9") (class "Default")
      (node (ref "R76") (pin "2") (pinfunction "2_2") (pintype "passive"))
    )
    (net (code "82") (name "DISP0_DAT10") (class "Default")
      (node (ref "R74") (pin "2") (pinfunction "2_2") (pintype "passive"))
    )
    (net (code "83") (name "DISP0_DAT11") (class "Default")
      (node (ref "R73") (pin "2") (pinfunction "2_2") (pintype "passive"))
    )
    (net (code "84") (name "DISP0_DAT12") (class "Default")
      (node (ref "R72") (pin "2") (pinfunction "2_2") (pintype "passive"))
    )
    (net (code "85") (name "DISP0_DAT13") (class "Default")
      (node (ref "R70") (pin "2") (pinfunction "2_2") (pintype "passive"))
    )
    (net (code "86") (name "DISP0_DAT14") (class "Default")
      (node (ref "R67") (pin "2") (pinfunction "2_2") (pintype "passive"))
    )
    (net (code "87") (name "DISP0_DAT15") (class "Default")
      (node (ref "R65") (pin "2") (pinfunction "2_2") (pintype "passive"))
    )
    (net (code "88") (name "DISP0_DAT16") (class "Default")
      (node (ref "R62") (pin "2") (pinfunction "2_2") (pintype "passive"))
    )
    (net (code "89") (name "DISP0_DAT17") (class "Default")
      (node (ref "R60") (pin "2") (pinfunction "2_2") (pintype "passive"))
    )
    (net (code "90") (name "DISP0_DAT18") (class "Default")
      (node (ref "R59") (pin "2") (pinfunction "2_2") (pintype "passive"))
    )
    (net (code "91") (name "DISP0_DAT19") (class "Default")
      (node (ref "R57") (pin "2") (pinfunction "2_2") (pintype "passive"))
    )
    (net (code "92") (name "DISP0_DAT20") (class "Default")
      (node (ref "R56") (pin "2") (pinfunction "2_2") (pintype "passive"))
    )
    (net (code "93") (name "DISP0_DAT21") (class "Default")
      (node (ref "R54") (pin "2") (pinfunction "2_2") (pintype "passive"))
    )
    (net (code "94") (name "DISP0_DAT22") (class "Default")
      (node (ref "R52") (pin "2") (pinfunction "2_2") (pintype "passive"))
    )
    (net (code "95") (name "DISP0_DAT23") (class "Default")
      (node (ref "R51") (pin "2") (pinfunction "2_2") (pintype "passive"))
    )
    (net (code "96") (name "DISP0_DRDY") (class "Default")
      (node (ref "R40") (pin "2") (pinfunction "2_2") (pintype "passive"))
    )
    (net (code "97") (name "DISP0_HSYNCH") (class "Default")
      (node (ref "R41") (pin "2") (pinfunction "2_2") (pintype "passive"))
    )
    (net (code "98") (name "DISP0_VSYNCH") (class "Default")
      (node (ref "R44") (pin "2") (pinfunction "2_2") (pintype "passive"))
    )
    (net (code "99") (name "DSI_CLK0M") (class "Default")
      (node (ref "U1") (pin "H3") (pinfunction "DSI_CLK0_N_H3") (pintype "output"))
    )
    (net (code "100") (name "DSI_CLK0P") (class "Default")
      (node (ref "U1") (pin "H4") (pinfunction "DSI_CLK0_P_H4") (pintype "output"))
    )
    (net (code "101") (name "DSI_D0M") (class "Default")
      (node (ref "U1") (pin "G2") (pinfunction "DSI_DATA0_N_G2") (pintype "output"))
    )
    (net (code "102") (name "DSI_D0P") (class "Default")
      (node (ref "U1") (pin "G1") (pinfunction "DSI_DATA0_P_G1") (pintype "output"))
    )
    (net (code "103") (name "DSI_D1M") (class "Default")
      (node (ref "U1") (pin "H2") (pinfunction "DSI_DATA1_N_H2") (pintype "output"))
    )
    (net (code "104") (name "DSI_D1P") (class "Default")
      (node (ref "U1") (pin "H1") (pinfunction "DSI_DATA1_P_H1") (pintype "output"))
    )
    (net (code "105") (name "GEN_2V5") (class "Default")
      (node (ref "R46") (pin "1") (pinfunction "1_1") (pintype "passive"))
      (node (ref "R50") (pin "1") (pinfunction "1_1") (pintype "passive"))
      (node (ref "R600") (pin "1") (pinfunction "1_1") (pintype "passive"))
      (node (ref "R87") (pin "1") (pinfunction "1_1") (pintype "passive"))
      (node (ref "U1") (pin "M7") (pinfunction "HDMI_VPH_M7") (pintype "power_in"))
    )
    (net (code "106") (name "GND") (class "Default")
      (node (ref "C39") (pin "2") (pinfunction "2_2") (pintype "passive"))
      (node (ref "C606") (pin "2") (pinfunction "2_2") (pintype "passive"))
      (node (ref "C607") (pin "2") (pinfunction "2_2") (pintype "passive"))
      (node (ref "C608") (pin "2") (pinfunction "2_2") (pintype "passive"))
      (node (ref "C609") (pin "2") (pinfunction "2_2") (pintype "passive"))
      (node (ref "C610") (pin "2") (pinfunction "2_2") (pintype "passive"))
      (node (ref "C625") (pin "2") (pinfunction "2_2") (pintype "passive"))
      (node (ref "C626") (pin "2") (pinfunction "2_2") (pintype "passive"))
      (node (ref "C632") (pin "2") (pinfunction "2_2") (pintype "passive"))
      (node (ref "C635") (pin "2") (pinfunction "2_2") (pintype "passive"))
      (node (ref "C638") (pin "2") (pinfunction "2_2") (pintype "passive"))
      (node (ref "C640") (pin "2") (pinfunction "2_2") (pintype "passive"))
      (node (ref "C668") (pin "2") (pinfunction "2_2") (pintype "passive"))
      (node (ref "C673") (pin "2") (pinfunction "2_2") (pintype "passive"))
      (node (ref "C678") (pin "2") (pinfunction "2_2") (pintype "passive"))
      (node (ref "C681") (pin "2") (pinfunction "2_2") (pintype "passive"))
      (node (ref "R37") (pin "2") (pinfunction "2_2") (pintype "passive"))
      (node (ref "R38") (pin "2") (pinfunction "2_2") (pintype "passive"))
      (node (ref "R604") (pin "2") (pinfunction "2_2") (pintype "passive"))
      (node (ref "R605") (pin "2") (pinfunction "2_2") (pintype "passive"))
      (node (ref "R619") (pin "2") (pinfunction "2_2") (pintype "passive"))
      (node (ref "R656") (pin "2") (pinfunction "2_2") (pintype "passive"))
    )
    (net (code "107") (name "HDMI_CLKM") (class "Default")
      (node (ref "U1") (pin "J5") (pinfunction "HDMI_TX_CLK_N_J5") (pintype "output"))
    )
    (net (code "108") (name "HDMI_CLKP") (class "Default")
      (node (ref "U1") (pin "J6") (pinfunction "HDMI_TX_CLK_P_J6") (pintype "output"))
    )
    (net (code "109") (name "HDMI_D0M") (class "Default")
      (node (ref "U1") (pin "K5") (pinfunction "HDMI_TX_DATA0_N_K5") (pintype "output"))
    )
    (net (code "110") (name "HDMI_D0P") (class "Default")
      (node (ref "U1") (pin "K6") (pinfunction "HDMI_TX_DATA0_P_K6") (pintype "output"))
    )
    (net (code "111") (name "HDMI_D1M") (class "Default")
      (node (ref "U1") (pin "J3") (pinfunction "HDMI_TX_DATA1_N_J3") (pintype "output"))
    )
    (net (code "112") (name "HDMI_D1P") (class "Default")
      (node (ref "U1") (pin "J4") (pinfunction "HDMI_TX_DATA1_P_J4") (pintype "output"))
    )
    (net (code "113") (name "HDMI_D2M") (class "Default")
      (node (ref "U1") (pin "K3") (pinfunction "HDMI_TX_DATA2_N_K3") (pintype "output"))
    )
    (net (code "114") (name "HDMI_D2P") (class "Default")
      (node (ref "U1") (pin "K4") (pinfunction "HDMI_TX_DATA2_P_K4") (pintype "output"))
    )
    (net (code "115") (name "HDMI_HPD") (class "Default")
      (node (ref "U1") (pin "K1") (pinfunction "HDMI_TX_HPD_K1") (pintype "input"))
    )
    (net (code "118") (name "LVDS0_CLK_N") (class "Default")
      (node (ref "U1") (pin "V4") (pinfunction "LVDS0_CLK_N_V4") (pintype "output"))
    )
    (net (code "119") (name "LVDS0_CLK_P") (class "Default")
      (node (ref "U1") (pin "V3") (pinfunction "LVDS0_CLK_P_V3") (pintype "output"))
    )
    (net (code "120") (name "LVDS0_TX0_N") (class "Default")
      (node (ref "U1") (pin "U2") (pinfunction "LVDS0_DATA0_N_U2") (pintype "output"))
    )
    (net (code "121") (name "LVDS0_TX0_P") (class "Default")
      (node (ref "U1") (pin "U1") (pinfunction "LVDS0_DATA0_P_U1") (pintype "output"))
    )
    (net (code "122") (name "LVDS0_TX1_N") (class "Default")
      (node (ref "U1") (pin "U4") (pinfunction "LVDS0_DATA1_N_U4") (pintype "output"))
    )
    (net (code "123") (name "LVDS0_TX1_P") (class "Default")
      (node (ref "U1") (pin "U3") (pinfunction "LVDS0_DATA1_P_U3") (pintype "output"))
    )
    (net (code "124") (name "LVDS0_TX2_N") (class "Default")
      (node (ref "U1") (pin "V2") (pinfunction "LVDS0_DATA2_N_V2") (pintype "output"))
    )
    (net (code "125") (name "LVDS0_TX2_P") (class "Default")
      (node (ref "U1") (pin "V1") (pinfunction "LVDS0_DATA2_P_V1") (pintype "output"))
    )
    (net (code "126") (name "LVDS1_CLK_N") (class "Default")
      (node (ref "U1") (pin "AB1") (pinfunction "LVDS1_DATA2_N_AB1") (pintype "output"))
    )
    (net (code "127") (name "LVDS1_CLK_P") (class "Default")
      (node (ref "U1") (pin "AB2") (pinfunction "LVDS1_DATA2_P_AB2") (pintype "output"))
    )
    (net (code "130") (name "LVDS1_TX1_N") (class "Default")
      (node (ref "U1") (pin "Y1") (pinfunction "LVDS1_DATA0_N_Y1") (pintype "output"))
    )
    (net (code "131") (name "LVDS1_TX1_P") (class "Default")
      (node (ref "U1") (pin "Y2") (pinfunction "LVDS1_DATA0_P_Y2") (pintype "output"))
    )
    (net (code "132") (name "LVDS1_TX2_N") (class "Default")
      (node (ref "U1") (pin "AA2") (pinfunction "LVDS1_DATA1_N_AA2") (pintype "output"))
    )
    (net (code "133") (name "LVDS1_TX2_P") (class "Default")
      (node (ref "U1") (pin "AA1") (pinfunction "LVDS1_DATA1_P_AA1") (pintype "output"))
    )
    (net (code "134") (name "PCIE_RXM") (class "Default")
      (node (ref "U1") (pin "B1") (pinfunction "PCIE_RX_N_B1") (pintype "input"))
    )
    (net (code "135") (name "PCIE_RXP") (class "Default")
      (node (ref "U1") (pin "B2") (pinfunction "PCIE_RX_P_B2") (pintype "input"))
    )
    (net (code "136") (name "PCIE_TXM") (class "Default")
      (node (ref "U1") (pin "A3") (pinfunction "PCIE_TX_N_A3") (pintype "output"))
    )
    (net (code "137") (name "PCIE_TXP") (class "Default")
      (node (ref "U1") (pin "B3") (pinfunction "PCIE_TX_P_B3") (pintype "output"))
    )
    (net (code "138") (name "PCIE_WAKE_B") (class "Default")
      (node (ref "U1") (pin "P3") (pinfunction "IPU1_CSI0_DATA_EN_/_EIM_DATA00_/_<GPIO5_IO20>_/_ARM_TRACE_CLK_P3") (pintype "bidirectional"))
    )
    (net (code "139") (name "RGMII_RXCLK") (class "Default")
      (node (ref "U1") (pin "B25") (pinfunction "USB_H3_STROBE_/_RGMII_RXC_/_<GPIO6_IO30>_B25") (pintype "input"))
    )
    (net (code "140") (name "RGMII_RXD0") (class "Default")
      (node (ref "U1") (pin "C24") (pinfunction "HSI_RX_READY_/_RGMII_RD0_/_<GPIO6_IO25>_C24") (pintype "input"))
    )
    (net (code "141") (name "RGMII_RXD1") (class "Default")
      (node (ref "U1") (pin "B23") (pinfunction "HSI_TX_FLAG_/_RGMII_RD1_/_<GPIO6_IO27>_B23") (pintype "input"))
    )
    (net (code "142") (name "RGMII_RXD2") (class "Default")
      (node (ref "U1") (pin "B24") (pinfunction "HSI_TX_DATA_/_RGMII_RD2_/_<GPIO6_IO28>_B24") (pintype "input"))
    )
    (net (code "143") (name "RGMII_RXD3") (class "Default")
      (node (ref "U1") (pin "D23") (pinfunction "HSI_TX_WAKE_/_RGMII_RD3_/_<GPIO6_IO29>_D23") (pintype "input"))
    )
    (net (code "144") (name "RGMII_RXDV") (class "Default")
      (node (ref "U1") (pin "D22") (pinfunction "USB_H3_DATA_/_RGMII_RX_CTL_/_<GPIO6_IO24>_D22") (pintype "input"))
    )
    (net (code "145") (name "RGMII_TXCLK") (class "Default")
      (node (ref "U1") (pin "D21") (pinfunction "USB_H2_DATA_/_RGMII_TXC_/_SPDIF_EXT_CLK_/_<GPIO6_IO19>_/_XTALOSC_REF_CLK_24M_D21") (pintype "output"))
    )
    (net (code "146") (name "RGMII_TXD0") (class "Default")
      (node (ref "U1") (pin "C22") (pinfunction "HSI_TX_READY_/_RGMII_TD0_/_<GPIO6_IO20>_C22") (pintype "output"))
    )
    (net (code "147") (name "RGMII_TXD1") (class "Default")
      (node (ref "U1") (pin "F20") (pinfunction "HSI_RX_FLAG_/_RGMII_TD1_/_<GPIO6_IO21>_F20") (pintype "output"))
    )
    (net (code "148") (name "RGMII_TXD2") (class "Default")
      (node (ref "U1") (pin "E21") (pinfunction "HSI_RX_DATA_/_RGMII_TD2_/_<GPIO6_IO22>_E21") (pintype "output"))
    )
    (net (code "149") (name "RGMII_TXD3") (class "Default")
      (node (ref "U1") (pin "A24") (pinfunction "HSI_RX_WAKE_/_RGMII_TD3_/_<GPIO6_IO23>_A24") (pintype "output"))
    )
    (net (code "150") (name "RGMII_TXEN") (class "Default")
      (node (ref "U1") (pin "C23") (pinfunction "USB_H2_STROBE_/_RGMII_TX_CTL_/_<GPIO6_IO26>_/_ENET_REF_CLK_C23") (pintype "output"))
    )
    (net (code "151") (name "SATA_RXN") (class "Default")
      (node (ref "U1") (pin "A14") (pinfunction "SATA_PHY_RX_N_A14") (pintype "input"))
    )
    (net (code "152") (name "SATA_RXP") (class "Default")
      (node (ref "U1") (pin "B14") (pinfunction "SATA_PHY_RX_P_B14") (pintype "input"))
    )
    (net (code "153") (name "SATA_TXN") (class "Default")
      (node (ref "U1") (pin "B12") (pinfunction "SATA_PHY_TX_N_B12") (pintype "output"))
    )
    (net (code "154") (name "SATA_TXP") (class "Default")
      (node (ref "U1") (pin "A12") (pinfunction "SATA_PHY_TX_P_A12") (pintype "output"))
    )
    (net (code "157") (name "VDDSOC_VP") (class "Default")
      (node (ref "L13") (pin "1") (pinfunction "1_1") (pintype "passive"))
      (node (ref "R48") (pin "1") (pinfunction "1_1") (pintype "passive"))
      (node (ref "R49") (pin "1") (pinfunction "1_1") (pintype "passive"))
      (node (ref "R96") (pin "1") (pinfunction "1_1") (pintype "passive"))
    )
    (net (code "158") (name "unconnected-(U1D-CSI_D2M-PadE1)") (class "Default")
      (node (ref "U1") (pin "E1") (pinfunction "CSI_D2M_E1") (pintype "input"))
    )
    (net (code "159") (name "unconnected-(U1D-CSI_D2P-PadE2)") (class "Default")
      (node (ref "U1") (pin "E2") (pinfunction "CSI_D2P_E2") (pintype "input"))
    )
    (net (code "160") (name "unconnected-(U1D-CSI_D3M-PadF2)") (class "Default")
      (node (ref "U1") (pin "F2") (pinfunction "CSI_D3M_F2") (pintype "input"))
    )
    (net (code "161") (name "unconnected-(U1D-CSI_D3P-PadF1)") (class "Default")
      (node (ref "U1") (pin "F1") (pinfunction "CSI_D3P_F1") (pintype "input"))
    )
    (net (code "162") (name "unconnected-(U1D-IPU1_CSI0_DATA04_{slash}_EIM_DATA02_{slash}_ECSPI1_SCLK_{slash}_KEY_COL5_{slash}_AUD3_TXC_{slash}_<GPIO5_IO22>_{slash}_ARM_TRACE01-PadN1)") (class "Default")
      (node (ref "U1") (pin "N1") (pinfunction "IPU1_CSI0_DATA04_/_EIM_DATA02_/_ECSPI1_SCLK_/_KEY_COL5_/_AUD3_TXC_/_<GPIO5_IO22>_/_ARM_TRACE01_N1") (pintype "bidirectional"))
    )
    (net (code "163") (name "unconnected-(U1D-IPU1_CSI0_DATA05_{slash}_EIM_DATA03_{slash}_ECSPI1_MOSI_{slash}_KEY_ROW5_{slash}_AUD3_TXD_{slash}_<GPIO5_IO23>_{slash}_ARM_TRACE02-PadP2)") (class "Default")
      (node (ref "U1") (pin "P2") (pinfunction "IPU1_CSI0_DATA05_/_EIM_DATA03_/_ECSPI1_MOSI_/_KEY_ROW5_/_AUD3_TXD_/_<GPIO5_IO23>_/_ARM_TRACE02_P2") (pintype "bidirectional"))
    )
    (net (code "164") (name "unconnected-(U1D-IPU1_CSI0_DATA06_{slash}_EIM_DATA04_{slash}_ECSPI1_MISO_{slash}_KEY_COL6_{slash}_AUD3_TXFS_{slash}_<GPIO5_IO24>_{slash}_ARM_TRACE03-PadN4)") (class "Default")
      (node (ref "U1") (pin "N4") (pinfunction "IPU1_CSI0_DATA06_/_EIM_DATA04_/_ECSPI1_MISO_/_KEY_COL6_/_AUD3_TXFS_/_<GPIO5_IO24>_/_ARM_TRACE03_N4") (pintype "bidirectional"))
    )
    (net (code "165") (name "unconnected-(U1D-IPU1_CSI0_DATA07_{slash}_EIM_DATA05_{slash}_ECSPI1_SS0_{slash}_KEY_ROW6_{slash}_AUD3_RXD_{slash}_<GPIO5_IO25>_{slash}_ARM_TRACE04-PadN3)") (class "Default")
      (node (ref "U1") (pin "N3") (pinfunction "IPU1_CSI0_DATA07_/_EIM_DATA05_/_ECSPI1_SS0_/_KEY_ROW6_/_AUD3_RXD_/_<GPIO5_IO25>_/_ARM_TRACE04_N3") (pintype "bidirectional"))
    )
    (net (code "166") (name "unconnected-(U1D-IPU1_CSI0_DATA08_{slash}_EIM_DATA06_{slash}_ECSPI2_SCLK_{slash}_KEY_COL7_{slash}_I2C1_SDA_{slash}_<GPIO5_IO26>_{slash}_ARM_TRACE05-PadN6)") (class "Default")
      (node (ref "U1") (pin "N6") (pinfunction "IPU1_CSI0_DATA08_/_EIM_DATA06_/_ECSPI2_SCLK_/_KEY_COL7_/_I2C1_SDA_/_<GPIO5_IO26>_/_ARM_TRACE05_N6") (pintype "bidirectional"))
    )
    (net (code "167") (name "unconnected-(U1D-IPU1_CSI0_DATA09_{slash}_EIM_DATA07_{slash}_ECSPI2_MOSI_{slash}_KEY_ROW7_{slash}_I2C1_SCL_{slash}_<GPIO5_IO27>_{slash}_ARM_TRACE06-PadN5)") (class "Default")
      (node (ref "U1") (pin "N5") (pinfunction "IPU1_CSI0_DATA09_/_EIM_DATA07_/_ECSPI2_MOSI_/_KEY_ROW7_/_I2C1_SCL_/_<GPIO5_IO27>_/_ARM_TRACE06_N5") (pintype "bidirectional"))
    )
    (net (code "168") (name "unconnected-(U1D-IPU1_CSI0_DATA10_{slash}_AUD3_RXC_{slash}_ECSPI2_MISO_{slash}_UART1_TX_DATA_{slash}_<GPIO5_IO28>_{slash}_ARM_TRACE07-PadM1)") (class "Default")
      (node (ref "U1") (pin "M1") (pinfunction "IPU1_CSI0_DATA10_/_AUD3_RXC_/_ECSPI2_MISO_/_UART1_TX_DATA_/_<GPIO5_IO28>_/_ARM_TRACE07_M1") (pintype "bidirectional"))
    )
    (net (code "169") (name "unconnected-(U1D-IPU1_CSI0_DATA11_{slash}_AUD3_RXFS_{slash}_ECSPI2_SS0_{slash}_UART1_RX_DATA_{slash}_<GPIO5_IO29>_{slash}_ARM_TRACE08-PadM3)") (class "Default")
      (node (ref "U1") (pin "M3") (pinfunction "IPU1_CSI0_DATA11_/_AUD3_RXFS_/_ECSPI2_SS0_/_UART1_RX_DATA_/_<GPIO5_IO29>_/_ARM_TRACE08_M3") (pintype "bidirectional"))
    )
    (net (code "170") (name "unconnected-(U1H-ESAI_RX_HF_CLK_{slash}_I2C3_SCL_{slash}_XTALOSC_REF_CLK_24M_{slash}_CCM_CLKO2_{slash}_<GPIO1_IO03>_{slash}_USB_H1_OC_{slash}_MLB_CLK-PadR7)") (class "Default")
      (node (ref "U1") (pin "R7") (pinfunction "ESAI_RX_HF_CLK_/_I2C3_SCL_/_XTALOSC_REF_CLK_24M_/_CCM_CLKO2_/_<GPIO1_IO03>_/_USB_H1_OC_/_MLB_CLK_R7") (pintype "bidirectional"))
    )
    (net (code "171") (name "unconnected-(U1H-ESAI_TX_CLK_{slash}_I2C3_SDA_{slash}_<GPIO1_IO06>_{slash}_SD2_LCTL_{slash}_MLB_SIG-PadT3)") (class "Default")
      (node (ref "U1") (pin "T3") (pinfunction "ESAI_TX_CLK_/_I2C3_SDA_/_<GPIO1_IO06>_/_SD2_LCTL_/_MLB_SIG_T3") (pintype "bidirectional"))
    )
    (net (code "172") (name "unconnected-(U1H-LVDS1_DATA3_N-PadAA3)") (class "Default")
      (node (ref "U1") (pin "AA3") (pinfunction "LVDS1_DATA3_N_AA3") (pintype "output"))
    )
    (net (code "173") (name "unconnected-(U1H-LVDS1_DATA3_P-PadAA4)") (class "Default")
      (node (ref "U1") (pin "AA4") (pinfunction "LVDS1_DATA3_P_AA4") (pintype "output"))
    )
    (net (code "174") (name "unconnected-(U1H-NAND_CE2_B_{slash}_IPU1_SISG0_{slash}_ESAI_TX0_{slash}_EIM_CRE_{slash}_CCM_CLKO2_{slash}_<GPIO6_IO15>-PadA17)") (class "Default")
      (node (ref "U1") (pin "A17") (pinfunction "NAND_CE2_B_/_IPU1_SISG0_/_ESAI_TX0_/_EIM_CRE_/_CCM_CLKO2_/_<GPIO6_IO15>_A17") (pintype "bidirectional"))
    )
    (net (code "175") (name "unconnected-(U1H-NVCC_LVDS2P5-PadV7)") (class "Default")
      (node (ref "U1") (pin "V7") (pinfunction "NVCC_LVDS2P5_V7") (pintype "power_in"))
    )
    (net (code "176") (name "unconnected-(U1H-SD1_DATA3_{slash}_GPT_COMPARE3_{slash}_PWM1_OUT_{slash}_WDOG2_B_{slash}_<GPIO1_IO21>_{slash}_WDOG2_RESET_B_DEB-PadF18)") (class "Default")
      (node (ref "U1") (pin "F18") (pinfunction "SD1_DATA3_/_GPT_COMPARE3_/_PWM1_OUT_/_WDOG2_B_/_<GPIO1_IO21>_/_WDOG2_RESET_B_DEB_F18") (pintype "bidirectional"))
    )
    (net (code "177") (name "unconnected-(U1I-ASRC_EXT_CLK_{slash}_HDMI_TX_DDC_SDA_{slash}_KEY_ROW3_{slash}_I2C2_SDA_{slash}_<GPIO4_IO13>_{slash}_SD1_VSELECT-PadT7)") (class "Default")
      (node (ref "U1") (pin "T7") (pinfunction "ASRC_EXT_CLK_/_HDMI_TX_DDC_SDA_/_KEY_ROW3_/_I2C2_SDA_/_<GPIO4_IO13>_/_SD1_VSELECT_T7") (pintype "bidirectional"))
    )
    (net (code "178") (name "unconnected-(U1I-ECSPI1_SS3_{slash}_ENET_CRS_{slash}_HDMI_TX_DDC_SCL_{slash}_KEY_COL3_{slash}_I2C2_SCL_{slash}_<GPIO4_IO12>_{slash}_SPDIF_IN-PadU5)") (class "Default")
      (node (ref "U1") (pin "U5") (pinfunction "ECSPI1_SS3_/_ENET_CRS_/_HDMI_TX_DDC_SCL_/_KEY_COL3_/_I2C2_SCL_/_<GPIO4_IO12>_/_SPDIF_IN_U5") (pintype "bidirectional"))
    )
    (net (code "179") (name "unconnected-(U1I-HDMI_REF-PadJ1)") (class "Default")
      (node (ref "U1") (pin "J1") (pinfunction "HDMI_REF_J1") (pintype "input"))
    )
    (net (code "180") (name "unconnected-(U1I-HDMI_VP-PadL7)") (class "Default")
      (node (ref "U1") (pin "L7") (pinfunction "HDMI_VP_L7") (pintype "power_in"))
    )
    (net (code "181") (name "unconnected-(U1K-ENET_MDIO_{slash}_ESAI_RX_CLK_{slash}_ENET_1588_EVENT1_OUT_{slash}_<GPIO1_IO22>_{slash}_SPDIF_LOCK-PadV23)") (class "Default")
      (node (ref "U1") (pin "V23") (pinfunction "ENET_MDIO_/_ESAI_RX_CLK_/_ENET_1588_EVENT1_OUT_/_<GPIO1_IO22>_/_SPDIF_LOCK_V23") (pintype "bidirectional"))
    )
    (net (code "182") (name "unconnected-(U1K-ENET_RX_EN_{slash}_ESAI_TX_CLK_{slash}_SPDIF_EXT_CLK_{slash}_<GPIO1_IO25>-PadU21)") (class "Default")
      (node (ref "U1") (pin "U21") (pinfunction "ENET_RX_EN_/_ESAI_TX_CLK_/_SPDIF_EXT_CLK_/_<GPIO1_IO25>_U21") (pintype "bidirectional"))
    )
    (net (code "183") (name "unconnected-(U1K-ENET_TX_CLK_{slash}_ESAI_RX_FS_{slash}_<GPIO1_IO23>_{slash}_SPDIF_SR_CLK-PadV22)") (class "Default")
      (node (ref "U1") (pin "V22") (pinfunction "ENET_TX_CLK_/_ESAI_RX_FS_/_<GPIO1_IO23>_/_SPDIF_SR_CLK_V22") (pintype "bidirectional"))
    )
    (net (code "184") (name "unconnected-(U1K-ENET_TX_EN_{slash}_ESAI_TX3_RX2_{slash}_<GPIO1_IO28>_{slash}_I2C4_SCL-PadV21)") (class "Default")
      (node (ref "U1") (pin "V21") (pinfunction "ENET_TX_EN_/_ESAI_TX3_RX2_/_<GPIO1_IO28>_/_I2C4_SCL_V21") (pintype "bidirectional"))
    )
    (net (code "185") (name "unconnected-(U1K-MLB_DATA_{slash}_ENET_MDC_{slash}_ESAI_TX5_RX0_{slash}_ENET_1588_EVENT1_IN_{slash}_<GPIO1_IO31>-PadV20)") (class "Default")
      (node (ref "U1") (pin "V20") (pinfunction "MLB_DATA_/_ENET_MDC_/_ESAI_TX5_RX0_/_ENET_1588_EVENT1_IN_/_<GPIO1_IO31>_V20") (pintype "bidirectional"))
    )
    (net (code "186") (name "unconnected-(U1K-MLB_SIG_{slash}_ENET_RX_DATA1_{slash}_ESAI_TX_FS_{slash}_ENET_1588_EVENT3_OUT_{slash}_<GPIO1_IO26>-PadW22)") (class "Default")
      (node (ref "U1") (pin "W22") (pinfunction "MLB_SIG_/_ENET_RX_DATA1_/_ESAI_TX_FS_/_ENET_1588_EVENT3_OUT_/_<GPIO1_IO26>_W22") (pintype "bidirectional"))
    )
  )
)
